# Power.net
KiCad netlist of a schematic drawn in Altium Designer
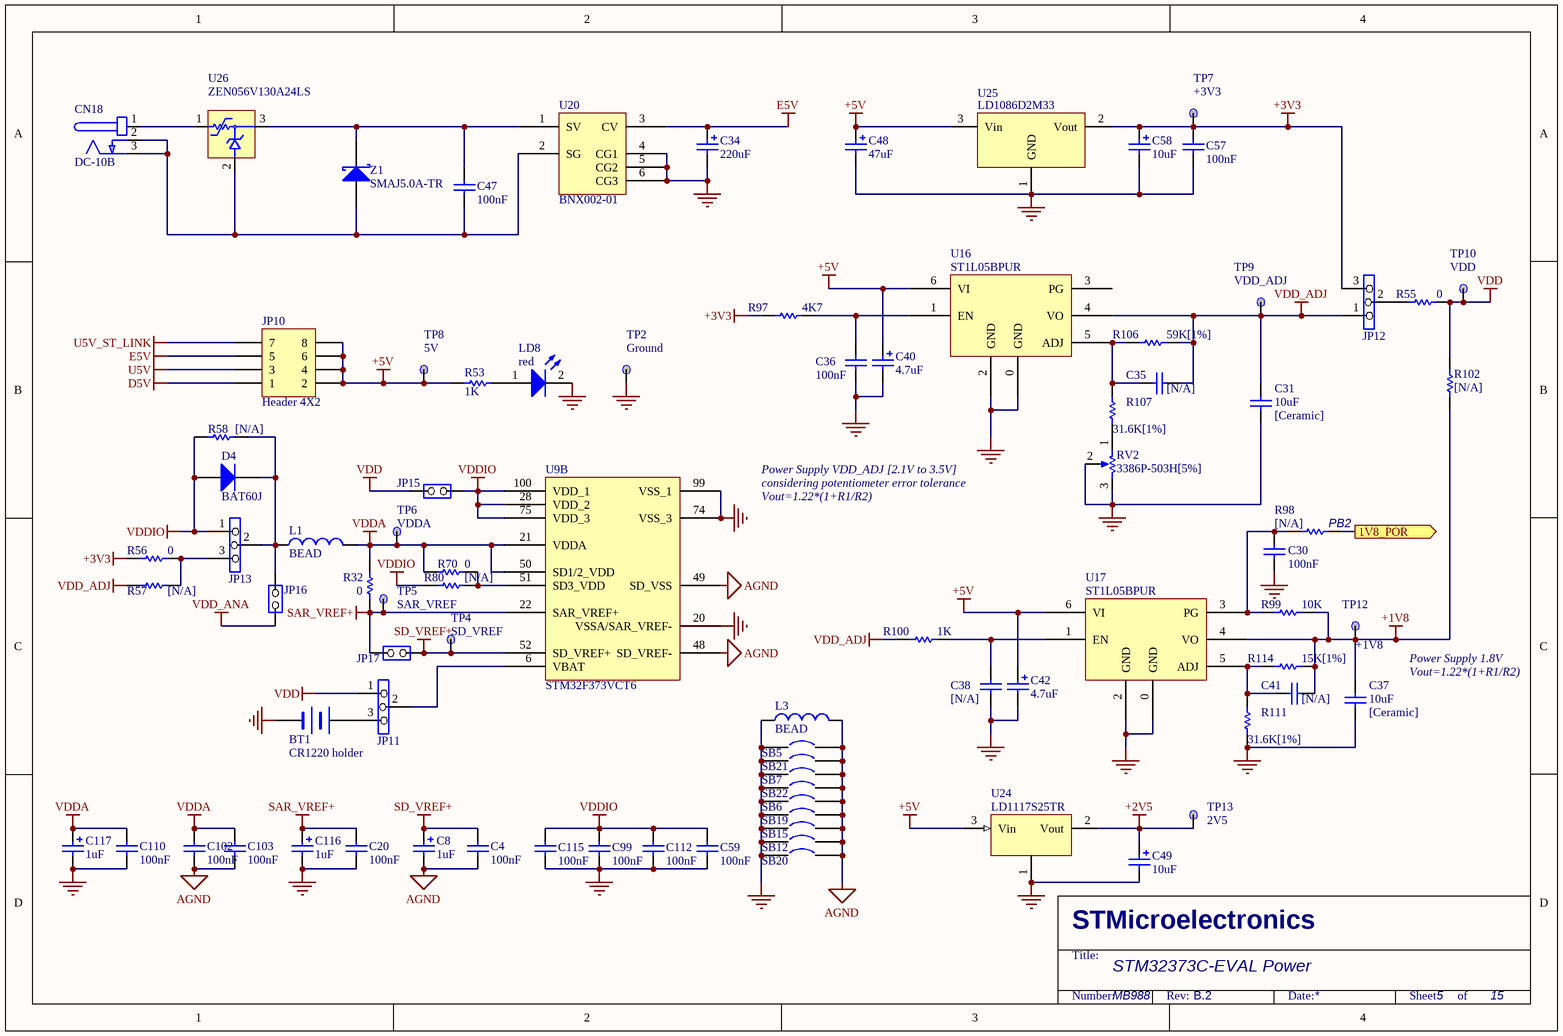
[diagram p0: Power.SchDoc]

(export (version "E")
  (design (tool "Eeschema 10.0.6"))
  (components
    (comp (ref "BT1")
      (value "CR1220 holder")
      (footprint "LI1220_1")
      (description "Battery")
      (libsource (lib "*") (part "BATTERY"))
    )
    (comp (ref "C4")
      (value "100nF")
      (footprint "0603C")
      (description "Capacitor")
      (fields (field (name "PUBLISHER") "Altium Limited"))
      (libsource (lib "Miscellaneous Devices") (part "Cap"))
    )
    (comp (ref "C8")
      (value "1uF")
      (footprint "TAN-A")
      (description "Polarized Capacitor (Radial)")
      (fields (field (name "PUBLISHER") "Altium Limited"))
      (libsource (lib "Miscellaneous Devices") (part "Cap Pol1"))
    )
    (comp (ref "C20")
      (value "100nF")
      (footprint "0603C")
      (description "Capacitor")
      (fields (field (name "PUBLISHER") "Altium Limited"))
      (libsource (lib "Miscellaneous Devices") (part "Cap"))
    )
    (comp (ref "C30")
      (value "100nF")
      (footprint "0603C")
      (description "Capacitor")
      (fields (field (name "PUBLISHER") "Altium Limited"))
      (libsource (lib "Miscellaneous Devices") (part "Cap"))
    )
    (comp (ref "C31")
      (value "10uF")
      (footprint "0805C")
      (description "Capacitor")
      (fields (field (name "PUBLISHER") "Altium Limited"))
      (libsource (lib "Miscellaneous Devices") (part "Cap"))
    )
    (comp (ref "C34")
      (value "220uF")
      (footprint "C310M")
      (description "Polarized Capacitor (Radial)")
      (fields (field (name "PUBLISHER") "Altium Limited"))
      (libsource (lib "Miscellaneous Devices") (part "Cap Pol1"))
    )
    (comp (ref "C35")
      (value "[N/A]")
      (footprint "0603C")
      (description "Capacitor")
      (fields (field (name "PUBLISHER") "Altium Limited"))
      (libsource (lib "Miscellaneous Devices") (part "Cap"))
    )
    (comp (ref "C36")
      (value "100nF")
      (footprint "0603C")
      (description "Capacitor")
      (fields (field (name "PUBLISHER") "Altium Limited"))
      (libsource (lib "Miscellaneous Devices") (part "Cap"))
    )
    (comp (ref "C37")
      (value "10uF")
      (footprint "0805C")
      (description "Capacitor")
      (fields (field (name "PUBLISHER") "Altium Limited"))
      (libsource (lib "Miscellaneous Devices") (part "Cap"))
    )
    (comp (ref "C38")
      (value "[N/A]")
      (footprint "0603C")
      (description "Capacitor")
      (fields (field (name "PUBLISHER") "Altium Limited"))
      (libsource (lib "Miscellaneous Devices") (part "Cap"))
    )
    (comp (ref "C40")
      (value "4.7uF")
      (footprint "TAN-A")
      (description "Polarized Capacitor (Radial)")
      (fields (field (name "PUBLISHER") "Altium Limited"))
      (libsource (lib "*") (part "Cap Pol1"))
    )
    (comp (ref "C41")
      (value "[N/A]")
      (footprint "0603C")
      (description "Capacitor")
      (fields (field (name "PUBLISHER") "Altium Limited"))
      (libsource (lib "Miscellaneous Devices") (part "Cap"))
    )
    (comp (ref "C42")
      (value "4.7uF")
      (footprint "TAN-A")
      (description "Polarized Capacitor (Radial)")
      (fields (field (name "PUBLISHER") "Altium Limited"))
      (libsource (lib "*") (part "Cap Pol1"))
    )
    (comp (ref "C47")
      (value "100nF")
      (footprint "0603C")
      (description "Capacitor")
      (fields (field (name "PUBLISHER") "Altium Limited"))
      (libsource (lib "Miscellaneous Devices") (part "CAP"))
    )
    (comp (ref "C48")
      (value "47uF")
      (footprint "C200M")
      (description "Polarized Capacitor (Radial)")
      (fields (field (name "PUBLISHER") "Altium Limited"))
      (libsource (lib "Miscellaneous Devices") (part "Cap Pol1"))
    )
    (comp (ref "C49")
      (value "10uF")
      (footprint "TAN-A")
      (description "Polarized Capacitor (Radial)")
      (fields (field (name "PUBLISHER") "Altium Limited"))
      (libsource (lib "Miscellaneous Devices") (part "Cap Pol1"))
    )
    (comp (ref "C57")
      (value "100nF")
      (footprint "0603C")
      (description "Capacitor")
      (fields (field (name "PUBLISHER") "Altium Limited"))
      (libsource (lib "Miscellaneous Devices") (part "Cap"))
    )
    (comp (ref "C58")
      (value "10uF")
      (footprint "TAN-A")
      (description "Polarized Capacitor (Radial)")
      (fields (field (name "PUBLISHER") "Altium Limited"))
      (libsource (lib "Miscellaneous Devices") (part "Cap Pol1"))
    )
    (comp (ref "C59")
      (value "100nF")
      (footprint "0603C")
      (description "Capacitor")
      (fields (field (name "PUBLISHER") "Altium Limited"))
      (libsource (lib "Miscellaneous Devices") (part "CAP"))
    )
    (comp (ref "C99")
      (value "100nF")
      (footprint "0603C")
      (description "Capacitor")
      (fields (field (name "PUBLISHER") "Altium Limited"))
      (libsource (lib "Miscellaneous Devices") (part "CAP"))
    )
    (comp (ref "C102")
      (value "100nF")
      (footprint "0603C")
      (description "Capacitor")
      (fields (field (name "PUBLISHER") "Altium Limited"))
      (libsource (lib "Miscellaneous Devices") (part "Cap"))
    )
    (comp (ref "C103")
      (value "100nF")
      (footprint "0603C")
      (description "Capacitor")
      (fields (field (name "PUBLISHER") "Altium Limited"))
      (libsource (lib "Miscellaneous Devices") (part "Cap"))
    )
    (comp (ref "C110")
      (value "100nF")
      (footprint "0603C")
      (description "Capacitor")
      (fields (field (name "PUBLISHER") "Altium Limited"))
      (libsource (lib "Miscellaneous Devices") (part "Cap"))
    )
    (comp (ref "C112")
      (value "100nF")
      (footprint "0603C")
      (description "Capacitor")
      (fields (field (name "PUBLISHER") "Altium Limited"))
      (libsource (lib "Miscellaneous Devices") (part "CAP"))
    )
    (comp (ref "C115")
      (value "100nF")
      (footprint "0603C")
      (description "Capacitor")
      (fields (field (name "PUBLISHER") "Altium Limited"))
      (libsource (lib "Miscellaneous Devices") (part "CAP"))
    )
    (comp (ref "C116")
      (value "1uF")
      (footprint "TAN-A")
      (description "Polarized Capacitor (Radial)")
      (fields (field (name "PUBLISHER") "Altium Limited"))
      (libsource (lib "Miscellaneous Devices") (part "Cap Pol1"))
    )
    (comp (ref "C117")
      (value "1uF")
      (footprint "TAN-A")
      (description "Polarized Capacitor (Radial)")
      (fields (field (name "PUBLISHER") "Altium Limited"))
      (libsource (lib "Miscellaneous Devices") (part "Cap Pol1"))
    )
    (comp (ref "CN18") (value "DC-10B") (footprint "DC10B") (libsource (lib "STR910_SCHLIB") (part "PJ202A")))
    (comp (ref "D4")
      (value "BAT60J")
      (footprint "SOD-323")
      (description "Default Diode")
      (fields (field (name "PUBLISHER") "Altium Limited"))
      (libsource (lib "Miscellaneous Devices") (part "Diode"))
    )
    (comp (ref "JP10")
      (value "Header 4X2")
      (footprint "2*4P")
      (description "Header, 4-Pin, Dual row")
      (fields (field (name "PUBLISHER") "Altium Limited"))
      (libsource (lib "Miscellaneous Connectors") (part "Header 4X2"))
    )
    (comp (ref "JP11") (value "~") (footprint "SIP3") (libsource (lib "") (part "Jumper3_1")))
    (comp (ref "JP12") (value "~") (footprint "SIP3") (libsource (lib "STR910_SCHLIB") (part "Jumper3")))
    (comp (ref "JP13") (value "~") (footprint "SIP3") (libsource (lib "STR910_SCHLIB") (part "Jumper3")))
    (comp (ref "JP15") (value "~") (footprint "SIP2") (libsource (lib "*") (part "JP2")))
    (comp (ref "JP16") (value "~") (footprint "SIP2") (libsource (lib "*") (part "JP2")))
    (comp (ref "JP17") (value "~") (footprint "SIP2") (libsource (lib "*") (part "JP2")))
    (comp (ref "L1")
      (value "BEAD")
      (footprint "0603L")
      (description "Inductor")
      (fields (field (name "PUBLISHER") "Altium Limited"))
      (libsource (lib "Miscellaneous Devices") (part "Inductor"))
    )
    (comp (ref "L3")
      (value "BEAD")
      (footprint "0603L")
      (description "Inductor")
      (fields (field (name "PUBLISHER") "Altium Limited"))
      (libsource (lib "Miscellaneous Devices") (part "Inductor"))
    )
    (comp (ref "LD8")
      (value "red")
      (footprint "0603D")
      (description "Typical RED, GREEN, YELLOW, AMBER GaAs LED")
      (fields (field (name "PUBLISHER") "Altium Limited"))
      (libsource (lib "Miscellaneous Devices") (part "LED2"))
    )
    (comp (ref "R32")
      (value "0")
      (footprint "0603R")
      (description "Resistor")
      (fields (field (name "PUBLISHER") "Altium Limited"))
      (libsource (lib "Miscellaneous Devices") (part "Res1"))
    )
    (comp (ref "R53")
      (value "1K")
      (footprint "0603R")
      (description "Resistor")
      (fields (field (name "PUBLISHER") "Altium Limited"))
      (libsource (lib "Miscellaneous Devices") (part "res1"))
    )
    (comp (ref "R55")
      (value "0")
      (footprint "0603R")
      (description "Resistor")
      (fields (field (name "PUBLISHER") "Altium Limited"))
      (libsource (lib "Miscellaneous Devices") (part "Res1"))
    )
    (comp (ref "R56")
      (value "0")
      (footprint "0603R")
      (description "Resistor")
      (fields (field (name "PUBLISHER") "Altium Limited"))
      (libsource (lib "Miscellaneous Devices") (part "Res1"))
    )
    (comp (ref "R57")
      (value "[N/A]")
      (footprint "0603R")
      (description "Resistor")
      (fields (field (name "PUBLISHER") "Altium Limited"))
      (libsource (lib "Miscellaneous Devices") (part "Res1"))
    )
    (comp (ref "R58")
      (value "[N/A]")
      (footprint "0603R")
      (description "Resistor")
      (fields (field (name "PUBLISHER") "Altium Limited"))
      (libsource (lib "Miscellaneous Devices") (part "Res1"))
    )
    (comp (ref "R70")
      (value "0")
      (footprint "0603R")
      (description "Resistor")
      (fields (field (name "PUBLISHER") "Altium Limited"))
      (libsource (lib "Miscellaneous Devices") (part "Res1"))
    )
    (comp (ref "R80")
      (value "[N/A]")
      (footprint "0603R")
      (description "Resistor")
      (fields (field (name "PUBLISHER") "Altium Limited"))
      (libsource (lib "Miscellaneous Devices") (part "Res1"))
    )
    (comp (ref "R97")
      (value "4K7")
      (footprint "0603R")
      (description "Resistor")
      (fields (field (name "PUBLISHER") "Altium Limited"))
      (libsource (lib "Miscellaneous Devices") (part "res1"))
    )
    (comp (ref "R98")
      (value "[N/A]")
      (footprint "0603R")
      (description "Resistor")
      (fields (field (name "PUBLISHER") "Altium Limited"))
      (libsource (lib "Miscellaneous Devices") (part "Res1"))
    )
    (comp (ref "R99")
      (value "10K")
      (footprint "0603R")
      (description "Resistor")
      (fields (field (name "PUBLISHER") "Altium Limited"))
      (libsource (lib "Miscellaneous Devices") (part "res1"))
    )
    (comp (ref "R100")
      (value "1K")
      (footprint "0603R")
      (description "Resistor")
      (fields (field (name "PUBLISHER") "Altium Limited"))
      (libsource (lib "Miscellaneous Devices") (part "res1"))
    )
    (comp (ref "R102")
      (value "[N/A]")
      (footprint "0603R")
      (description "Resistor")
      (fields (field (name "PUBLISHER") "Altium Limited"))
      (libsource (lib "Miscellaneous Devices") (part "Res1"))
    )
    (comp (ref "R106")
      (value "59K[1%]")
      (footprint "0603R")
      (description "Resistor")
      (fields (field (name "PUBLISHER") "Altium Limited"))
      (libsource (lib "Miscellaneous Devices") (part "Res1"))
    )
    (comp (ref "R107")
      (value "31.6K[1%]")
      (footprint "0603R")
      (description "Resistor")
      (fields (field (name "PUBLISHER") "Altium Limited"))
      (libsource (lib "Miscellaneous Devices") (part "Res1"))
    )
    (comp (ref "R111")
      (value "31.6K[1%]")
      (footprint "0603R")
      (description "Resistor")
      (fields (field (name "PUBLISHER") "Altium Limited"))
      (libsource (lib "Miscellaneous Devices") (part "Res1"))
    )
    (comp (ref "R114")
      (value "15K[1%]")
      (footprint "0603R")
      (description "Resistor")
      (fields (field (name "PUBLISHER") "Altium Limited"))
      (libsource (lib "Miscellaneous Devices") (part "Res1"))
    )
    (comp (ref "RV2")
      (value "3386P-503H[5%]")
      (footprint "3296W")
      (libsource (lib "STR910_SCHLIB") (part "RV"))
    )
    (comp (ref "SB5")
      (value "~")
      (footprint "JP2_SMD")
      (description "Circuit Breaker")
      (fields (field (name "PUBLISHER") "Altium Limited"))
      (libsource (lib "Miscellaneous Devices") (part "Circuit Breaker"))
    )
    (comp (ref "SB6")
      (value "~")
      (footprint "JP2_SMD")
      (description "Circuit Breaker")
      (fields (field (name "PUBLISHER") "Altium Limited"))
      (libsource (lib "Miscellaneous Devices") (part "Circuit Breaker"))
    )
    (comp (ref "SB7")
      (value "~")
      (footprint "JP2_SMD")
      (description "Circuit Breaker")
      (fields (field (name "PUBLISHER") "Altium Limited"))
      (libsource (lib "Miscellaneous Devices") (part "Circuit Breaker"))
    )
    (comp (ref "SB12")
      (value "~")
      (footprint "JP2_SMD")
      (description "Circuit Breaker")
      (fields (field (name "PUBLISHER") "Altium Limited"))
      (libsource (lib "Miscellaneous Devices") (part "Circuit Breaker"))
    )
    (comp (ref "SB15")
      (value "~")
      (footprint "JP2_SMD")
      (description "Circuit Breaker")
      (fields (field (name "PUBLISHER") "Altium Limited"))
      (libsource (lib "Miscellaneous Devices") (part "Circuit Breaker"))
    )
    (comp (ref "SB19")
      (value "~")
      (footprint "JP2_SMD")
      (description "Circuit Breaker")
      (fields (field (name "PUBLISHER") "Altium Limited"))
      (libsource (lib "Miscellaneous Devices") (part "Circuit Breaker"))
    )
    (comp (ref "SB20")
      (value "~")
      (footprint "JP2_SMD")
      (description "Circuit Breaker")
      (fields (field (name "PUBLISHER") "Altium Limited"))
      (libsource (lib "Miscellaneous Devices") (part "Circuit Breaker"))
    )
    (comp (ref "SB21")
      (value "~")
      (footprint "JP2_SMD")
      (description "Circuit Breaker")
      (fields (field (name "PUBLISHER") "Altium Limited"))
      (libsource (lib "Miscellaneous Devices") (part "Circuit Breaker"))
    )
    (comp (ref "SB22")
      (value "~")
      (footprint "JP2_SMD")
      (description "Circuit Breaker")
      (fields (field (name "PUBLISHER") "Altium Limited"))
      (libsource (lib "Miscellaneous Devices") (part "Circuit Breaker"))
    )
    (comp (ref "TP2") (value "Ground") (footprint "TP") (libsource (lib "*") (part "TP")))
    (comp (ref "TP4") (value "SD_VREF") (footprint "TP") (libsource (lib "*") (part "TP")))
    (comp (ref "TP5") (value "SAR_VREF") (footprint "TP") (libsource (lib "*") (part "TP")))
    (comp (ref "TP6") (value "VDDA") (footprint "TP") (libsource (lib "*") (part "TP")))
    (comp (ref "TP7") (value "+3V3") (footprint "TP") (libsource (lib "*") (part "TP")))
    (comp (ref "TP8") (value "5V") (footprint "TP") (libsource (lib "*") (part "TP")))
    (comp (ref "TP9") (value "VDD_ADJ") (footprint "TP") (libsource (lib "*") (part "TP")))
    (comp (ref "TP10") (value "VDD") (footprint "TP") (libsource (lib "*") (part "TP")))
    (comp (ref "TP12") (value "+1V8") (footprint "TP") (libsource (lib "*") (part "TP")))
    (comp (ref "TP13") (value "2V5") (footprint "TP") (libsource (lib "*") (part "TP")))
    (comp (ref "U9")
      (value "STM32F373VCT6")
      (footprint "IC149-100-025-B5")
      (libsource (lib "MB988") (part "Goldfish"))
    )
    (comp (ref "U16") (value "ST1L05BPUR") (footprint "DFN6(3X3)") (libsource (lib "*") (part "ST1L05")))
    (comp (ref "U17") (value "ST1L05BPUR") (footprint "DFN6(3X3)") (libsource (lib "*") (part "ST1L05")))
    (comp (ref "U20")
      (value "BNX002-01")
      (footprint "BNX001")
      (libsource (lib "STR910_SCHLIB") (part "BNX002"))
    )
    (comp (ref "U24") (value "LD1117S25TR") (footprint "SOT-223") (libsource (lib "*") (part "LD1117")))
    (comp (ref "U25") (value "LD1086D2M33") (footprint "D2PAK/A") (libsource (lib "*") (part "VOLTREG1")))
    (comp (ref "U26")
      (value "ZEN056V130A24LS")
      (footprint "polyzen")
      (libsource (lib "STR910_SCHLIB") (part "ZEN056V130A24LS"))
    )
    (comp (ref "Z1")
      (value "SMAJ5.0A-TR")
      (footprint "1R1C")
      (description "Schottky Diode")
      (fields (field (name "PUBLISHER") "Altium Limited"))
      (libsource (lib "Miscellaneous Devices") (part "D Schottky"))
    )
  )
  (nets
    (net (code "1") (name "+1V8") (class "Default")
      (node (ref "C37") (pin "1") (pinfunction "1_1") (pintype "passive"))
      (node (ref "C41") (pin "2") (pinfunction "2_2") (pintype "passive"))
      (node (ref "R102") (pin "2") (pinfunction "2_2") (pintype "passive"))
      (node (ref "R114") (pin "1") (pinfunction "1_1") (pintype "passive"))
      (node (ref "R99") (pin "2") (pinfunction "2_2") (pintype "passive"))
      (node (ref "TP12") (pin "1") (pinfunction "1_1") (pintype "passive"))
      (node (ref "U17") (pin "4") (pinfunction "VO_4") (pintype "passive"))
    )
    (net (code "2") (name "+2V5") (class "Default")
      (node (ref "C49") (pin "1") (pinfunction "1_1") (pintype "passive"))
      (node (ref "TP13") (pin "1") (pinfunction "1_1") (pintype "passive"))
      (node (ref "U24") (pin "2") (pinfunction "Vout_2") (pintype "power_in"))
    )
    (net (code "3") (name "+3V3") (class "Default")
      (node (ref "C57") (pin "1") (pinfunction "1_1") (pintype "passive"))
      (node (ref "C58") (pin "1") (pinfunction "1_1") (pintype "passive"))
      (node (ref "JP12") (pin "3") (pintype "passive"))
      (node (ref "R56") (pin "2") (pinfunction "2_2") (pintype "passive"))
      (node (ref "R97") (pin "2") (pinfunction "2_2") (pintype "passive"))
      (node (ref "TP7") (pin "1") (pinfunction "1_1") (pintype "passive"))
      (node (ref "U25") (pin "2") (pinfunction "Vout_2") (pintype "passive"))
    )
    (net (code "4") (name "+5V") (class "Default")
      (node (ref "C40") (pin "1") (pinfunction "1_1") (pintype "passive"))
      (node (ref "C42") (pin "1") (pinfunction "1_1") (pintype "passive"))
      (node (ref "C48") (pin "1") (pinfunction "1_1") (pintype "passive"))
      (node (ref "JP10") (pin "2") (pinfunction "2_2") (pintype "passive"))
      (node (ref "JP10") (pin "4") (pinfunction "4_4") (pintype "passive"))
      (node (ref "JP10") (pin "6") (pinfunction "6_6") (pintype "passive"))
      (node (ref "JP10") (pin "8") (pinfunction "8_8") (pintype "passive"))
      (node (ref "R53") (pin "2") (pinfunction "2_2") (pintype "passive"))
      (node (ref "TP8") (pin "1") (pinfunction "1_1") (pintype "passive"))
      (node (ref "U16") (pin "6") (pinfunction "VI_6") (pintype "passive"))
      (node (ref "U17") (pin "6") (pinfunction "VI_6") (pintype "passive"))
      (node (ref "U24") (pin "3") (pinfunction "Vin_3") (pintype "input"))
      (node (ref "U25") (pin "3") (pinfunction "Vin_3") (pintype "passive"))
    )
    (net (code "5") (name "/1V8_POR") (class "Default")
      (node (ref "R98") (pin "1") (pinfunction "1_1") (pintype "passive"))
    )
    (net (code "6") (name "AGND") (class "Default")
      (node (ref "C102") (pin "1") (pinfunction "1_1") (pintype "passive"))
      (node (ref "C103") (pin "1") (pinfunction "1_1") (pintype "passive"))
      (node (ref "C4") (pin "1") (pinfunction "1_1") (pintype "passive"))
      (node (ref "C8") (pin "2") (pinfunction "2_2") (pintype "passive"))
      (node (ref "L3") (pin "2") (pinfunction "2_2") (pintype "passive"))
      (node (ref "SB12") (pin "2") (pinfunction "2_2") (pintype "passive"))
      (node (ref "SB15") (pin "2") (pinfunction "2_2") (pintype "passive"))
      (node (ref "SB19") (pin "2") (pinfunction "2_2") (pintype "passive"))
      (node (ref "SB20") (pin "2") (pinfunction "2_2") (pintype "passive"))
      (node (ref "SB21") (pin "2") (pinfunction "2_2") (pintype "passive"))
      (node (ref "SB22") (pin "2") (pinfunction "2_2") (pintype "passive"))
      (node (ref "SB5") (pin "2") (pinfunction "2_2") (pintype "passive"))
      (node (ref "SB6") (pin "2") (pinfunction "2_2") (pintype "passive"))
      (node (ref "SB7") (pin "2") (pinfunction "2_2") (pintype "passive"))
      (node (ref "U9") (pin "48") (pinfunction "SD_VREF-_48") (pintype "passive"))
      (node (ref "U9") (pin "49") (pinfunction "SD_VSS_49") (pintype "passive"))
    )
    (net (code "7") (name "D5V") (class "Default")
      (node (ref "JP10") (pin "1") (pinfunction "1_1") (pintype "passive"))
    )
    (net (code "8") (name "E5V") (class "Default")
      (node (ref "C34") (pin "1") (pinfunction "1_1") (pintype "passive"))
      (node (ref "JP10") (pin "5") (pinfunction "5_5") (pintype "passive"))
      (node (ref "U20") (pin "3") (pinfunction "CV_3") (pintype "passive"))
    )
    (net (code "9") (name "GND") (class "Default")
      (node (ref "BT1") (pin "2") (pinfunction "-_2") (pintype "passive"))
      (node (ref "C110") (pin "1") (pinfunction "1_1") (pintype "passive"))
      (node (ref "C112") (pin "2") (pinfunction "2_2") (pintype "passive"))
      (node (ref "C115") (pin "2") (pinfunction "2_2") (pintype "passive"))
      (node (ref "C116") (pin "2") (pinfunction "2_2") (pintype "passive"))
      (node (ref "C117") (pin "2") (pinfunction "2_2") (pintype "passive"))
      (node (ref "C20") (pin "1") (pinfunction "1_1") (pintype "passive"))
      (node (ref "C30") (pin "2") (pinfunction "2_2") (pintype "passive"))
      (node (ref "C31") (pin "2") (pinfunction "2_2") (pintype "passive"))
      (node (ref "C34") (pin "2") (pinfunction "2_2") (pintype "passive"))
      (node (ref "C36") (pin "2") (pinfunction "2_2") (pintype "passive"))
      (node (ref "C37") (pin "2") (pinfunction "2_2") (pintype "passive"))
      (node (ref "C38") (pin "2") (pinfunction "2_2") (pintype "passive"))
      (node (ref "C40") (pin "2") (pinfunction "2_2") (pintype "passive"))
      (node (ref "C42") (pin "2") (pinfunction "2_2") (pintype "passive"))
      (node (ref "C48") (pin "2") (pinfunction "2_2") (pintype "passive"))
      (node (ref "C49") (pin "2") (pinfunction "2_2") (pintype "passive"))
      (node (ref "C57") (pin "2") (pinfunction "2_2") (pintype "passive"))
      (node (ref "C58") (pin "2") (pinfunction "2_2") (pintype "passive"))
      (node (ref "C59") (pin "2") (pinfunction "2_2") (pintype "passive"))
      (node (ref "C99") (pin "2") (pinfunction "2_2") (pintype "passive"))
      (node (ref "L3") (pin "1") (pinfunction "1_1") (pintype "passive"))
      (node (ref "LD8") (pin "2") (pinfunction "K_2") (pintype "passive"))
      (node (ref "R111") (pin "2") (pinfunction "2_2") (pintype "passive"))
      (node (ref "RV2") (pin "2") (pinfunction "TAP_2") (pintype "passive"))
      (node (ref "RV2") (pin "3") (pinfunction "TOP_3") (pintype "passive"))
      (node (ref "SB12") (pin "1") (pinfunction "1_1") (pintype "passive"))
      (node (ref "SB15") (pin "1") (pinfunction "1_1") (pintype "passive"))
      (node (ref "SB19") (pin "1") (pinfunction "1_1") (pintype "passive"))
      (node (ref "SB20") (pin "1") (pinfunction "1_1") (pintype "passive"))
      (node (ref "SB21") (pin "1") (pinfunction "1_1") (pintype "passive"))
      (node (ref "SB22") (pin "1") (pinfunction "1_1") (pintype "passive"))
      (node (ref "SB5") (pin "1") (pinfunction "1_1") (pintype "passive"))
      (node (ref "SB6") (pin "1") (pinfunction "1_1") (pintype "passive"))
      (node (ref "SB7") (pin "1") (pinfunction "1_1") (pintype "passive"))
      (node (ref "TP2") (pin "1") (pinfunction "1_1") (pintype "passive"))
      (node (ref "U16") (pin "0") (pinfunction "GND_0") (pintype "passive"))
      (node (ref "U16") (pin "2") (pinfunction "GND_2") (pintype "passive"))
      (node (ref "U17") (pin "0") (pinfunction "GND_0") (pintype "passive"))
      (node (ref "U17") (pin "2") (pinfunction "GND_2") (pintype "passive"))
      (node (ref "U20") (pin "4") (pinfunction "CG1_4") (pintype "passive"))
      (node (ref "U20") (pin "5") (pinfunction "CG2_5") (pintype "passive"))
      (node (ref "U20") (pin "6") (pinfunction "CG3_6") (pintype "passive"))
      (node (ref "U24") (pin "1") (pintype "passive"))
      (node (ref "U25") (pin "1") (pinfunction "GND_1") (pintype "passive"))
      (node (ref "U9") (pin "20") (pinfunction "VSSA/SAR_VREF-_20") (pintype "passive"))
      (node (ref "U9") (pin "74") (pinfunction "VSS_3_74") (pintype "passive"))
      (node (ref "U9") (pin "99") (pinfunction "VSS_1_99") (pintype "passive"))
    )
    (net (code "10") (name "Net-(BT1-+)") (class "Default")
      (node (ref "BT1") (pin "1") (pinfunction "+_1") (pintype "passive"))
      (node (ref "JP11") (pin "3") (pintype "passive"))
    )
    (net (code "11") (name "Net-(CN18-+)") (class "Default")
      (node (ref "CN18") (pin "1") (pinfunction "+_1") (pintype "passive"))
      (node (ref "U26") (pin "1") (pintype "passive"))
    )
    (net (code "12") (name "Net-(D4-K)") (class "Default")
      (node (ref "D4") (pin "2") (pinfunction "K_2") (pintype "passive"))
      (node (ref "JP13") (pin "2") (pintype "passive"))
      (node (ref "JP16") (pin "2") (pinfunction "NO_2") (pintype "passive"))
      (node (ref "L1") (pin "1") (pinfunction "1_1") (pintype "passive"))
      (node (ref "R58") (pin "2") (pinfunction "2_2") (pintype "passive"))
    )
    (net (code "13") (name "Net-(JP12-Pad2)") (class "Default")
      (node (ref "JP12") (pin "2") (pintype "passive"))
      (node (ref "R55") (pin "2") (pinfunction "2_2") (pintype "passive"))
    )
    (net (code "14") (name "Net-(JP13-Pad3)") (class "Default")
      (node (ref "JP13") (pin "3") (pintype "passive"))
      (node (ref "R56") (pin "1") (pinfunction "1_1") (pintype "passive"))
      (node (ref "R57") (pin "1") (pinfunction "1_1") (pintype "passive"))
    )
    (net (code "15") (name "Net-(LD8-A)") (class "Default")
      (node (ref "LD8") (pin "1") (pinfunction "A_1") (pintype "passive"))
      (node (ref "R53") (pin "1") (pinfunction "1_1") (pintype "passive"))
    )
    (net (code "16") (name "Net-(RV2-BOT)") (class "Default")
      (node (ref "R107") (pin "2") (pinfunction "2_2") (pintype "passive"))
      (node (ref "RV2") (pin "1") (pinfunction "BOT_1") (pintype "passive"))
    )
    (net (code "17") (name "Net-(U9B-SD3_VDD)") (class "Default")
      (node (ref "R70") (pin "2") (pinfunction "2_2") (pintype "passive"))
      (node (ref "R80") (pin "2") (pinfunction "2_2") (pintype "passive"))
      (node (ref "U9") (pin "51") (pinfunction "SD3_VDD_51") (pintype "passive"))
    )
    (net (code "18") (name "Net-(U9B-VBAT)") (class "Default")
      (node (ref "JP11") (pin "2") (pintype "passive"))
      (node (ref "U9") (pin "6") (pinfunction "VBAT_6") (pintype "passive"))
    )
    (net (code "19") (name "Net-(U16-ADJ)") (class "Default")
      (node (ref "C35") (pin "1") (pinfunction "1_1") (pintype "passive"))
      (node (ref "R106") (pin "2") (pinfunction "2_2") (pintype "passive"))
      (node (ref "R107") (pin "1") (pinfunction "1_1") (pintype "passive"))
      (node (ref "U16") (pin "5") (pinfunction "ADJ_5") (pintype "passive"))
    )
    (net (code "20") (name "Net-(U16-EN)") (class "Default")
      (node (ref "C36") (pin "1") (pinfunction "1_1") (pintype "passive"))
      (node (ref "R97") (pin "1") (pinfunction "1_1") (pintype "passive"))
      (node (ref "U16") (pin "1") (pinfunction "EN_1") (pintype "passive"))
    )
    (net (code "21") (name "Net-(U17-ADJ)") (class "Default")
      (node (ref "C41") (pin "1") (pinfunction "1_1") (pintype "passive"))
      (node (ref "R111") (pin "1") (pinfunction "1_1") (pintype "passive"))
      (node (ref "R114") (pin "2") (pinfunction "2_2") (pintype "passive"))
      (node (ref "U17") (pin "5") (pinfunction "ADJ_5") (pintype "passive"))
    )
    (net (code "22") (name "Net-(U17-EN)") (class "Default")
      (node (ref "C38") (pin "1") (pinfunction "1_1") (pintype "passive"))
      (node (ref "R100") (pin "1") (pinfunction "1_1") (pintype "passive"))
      (node (ref "U17") (pin "1") (pinfunction "EN_1") (pintype "passive"))
    )
    (net (code "23") (name "Net-(U17-PG)") (class "Default")
      (node (ref "C30") (pin "1") (pinfunction "1_1") (pintype "passive"))
      (node (ref "R98") (pin "2") (pinfunction "2_2") (pintype "passive"))
      (node (ref "R99") (pin "1") (pinfunction "1_1") (pintype "passive"))
      (node (ref "U17") (pin "3") (pinfunction "PG_3") (pintype "passive"))
    )
    (net (code "24") (name "Net-(U20-SG)") (class "Default")
      (node (ref "C47") (pin "2") (pinfunction "2_2") (pintype "passive"))
      (node (ref "CN18") (pin "2") (pinfunction "GND_2") (pintype "passive"))
      (node (ref "CN18") (pin "3") (pinfunction "GND_3") (pintype "passive"))
      (node (ref "U20") (pin "2") (pinfunction "SG_2") (pintype "passive"))
      (node (ref "U26") (pin "2") (pintype "passive"))
      (node (ref "Z1") (pin "1") (pinfunction "A_1") (pintype "passive"))
    )
    (net (code "25") (name "Net-(U20-SV)") (class "Default")
      (node (ref "C47") (pin "1") (pinfunction "1_1") (pintype "passive"))
      (node (ref "U20") (pin "1") (pinfunction "SV_1") (pintype "passive"))
      (node (ref "U26") (pin "3") (pintype "passive"))
      (node (ref "Z1") (pin "2") (pinfunction "K_2") (pintype "passive"))
    )
    (net (code "26") (name "SAR_VREF+") (class "Default")
      (node (ref "C116") (pin "1") (pinfunction "1_1") (pintype "passive"))
      (node (ref "C20") (pin "2") (pinfunction "2_2") (pintype "passive"))
      (node (ref "JP17") (pin "2") (pinfunction "NO_2") (pintype "passive"))
      (node (ref "R32") (pin "2") (pinfunction "2_2") (pintype "passive"))
      (node (ref "TP5") (pin "1") (pinfunction "1_1") (pintype "passive"))
      (node (ref "U9") (pin "22") (pinfunction "SAR_VREF+_22") (pintype "passive"))
    )
    (net (code "27") (name "SD_VREF+") (class "Default")
      (node (ref "C4") (pin "2") (pinfunction "2_2") (pintype "passive"))
      (node (ref "C8") (pin "1") (pinfunction "1_1") (pintype "passive"))
      (node (ref "JP17") (pin "1") (pinfunction "COMMON_1") (pintype "passive"))
      (node (ref "TP4") (pin "1") (pinfunction "1_1") (pintype "passive"))
      (node (ref "U9") (pin "52") (pinfunction "SD_VREF+_52") (pintype "passive"))
    )
    (net (code "28") (name "U5V") (class "Default")
      (node (ref "JP10") (pin "3") (pinfunction "3_3") (pintype "passive"))
    )
    (net (code "29") (name "U5V_ST_LINK") (class "Default")
      (node (ref "JP10") (pin "7") (pinfunction "7_7") (pintype "passive"))
    )
    (net (code "30") (name "VDD") (class "Default")
      (node (ref "JP11") (pin "1") (pintype "passive"))
      (node (ref "JP15") (pin "2") (pinfunction "NO_2") (pintype "passive"))
      (node (ref "R102") (pin "1") (pinfunction "1_1") (pintype "passive"))
      (node (ref "R55") (pin "1") (pinfunction "1_1") (pintype "passive"))
      (node (ref "TP10") (pin "1") (pinfunction "1_1") (pintype "passive"))
    )
    (net (code "31") (name "VDDA") (class "Default")
      (node (ref "C102") (pin "2") (pinfunction "2_2") (pintype "passive"))
      (node (ref "C103") (pin "2") (pinfunction "2_2") (pintype "passive"))
      (node (ref "C110") (pin "2") (pinfunction "2_2") (pintype "passive"))
      (node (ref "C117") (pin "1") (pinfunction "1_1") (pintype "passive"))
      (node (ref "L1") (pin "2") (pinfunction "2_2") (pintype "passive"))
      (node (ref "R32") (pin "1") (pinfunction "1_1") (pintype "passive"))
      (node (ref "R70") (pin "1") (pinfunction "1_1") (pintype "passive"))
      (node (ref "TP6") (pin "1") (pinfunction "1_1") (pintype "passive"))
      (node (ref "U9") (pin "21") (pinfunction "VDDA_21") (pintype "passive"))
      (node (ref "U9") (pin "50") (pinfunction "SD1/2_VDD_50") (pintype "passive"))
    )
    (net (code "32") (name "VDDIO") (class "Default")
      (node (ref "C112") (pin "1") (pinfunction "1_1") (pintype "passive"))
      (node (ref "C115") (pin "1") (pinfunction "1_1") (pintype "passive"))
      (node (ref "C59") (pin "1") (pinfunction "1_1") (pintype "passive"))
      (node (ref "C99") (pin "1") (pinfunction "1_1") (pintype "passive"))
      (node (ref "D4") (pin "1") (pinfunction "A_1") (pintype "passive"))
      (node (ref "JP13") (pin "1") (pintype "passive"))
      (node (ref "JP15") (pin "1") (pinfunction "COMMON_1") (pintype "passive"))
      (node (ref "R58") (pin "1") (pinfunction "1_1") (pintype "passive"))
      (node (ref "R80") (pin "1") (pinfunction "1_1") (pintype "passive"))
      (node (ref "U9") (pin "100") (pinfunction "VDD_1_100") (pintype "passive"))
      (node (ref "U9") (pin "28") (pinfunction "VDD_2_28") (pintype "passive"))
      (node (ref "U9") (pin "75") (pinfunction "VDD_3_75") (pintype "passive"))
    )
    (net (code "33") (name "VDD_ADJ") (class "Default")
      (node (ref "C31") (pin "1") (pinfunction "1_1") (pintype "passive"))
      (node (ref "C35") (pin "2") (pinfunction "2_2") (pintype "passive"))
      (node (ref "JP12") (pin "1") (pintype "passive"))
      (node (ref "R100") (pin "2") (pinfunction "2_2") (pintype "passive"))
      (node (ref "R106") (pin "1") (pinfunction "1_1") (pintype "passive"))
      (node (ref "R57") (pin "2") (pinfunction "2_2") (pintype "passive"))
      (node (ref "TP9") (pin "1") (pinfunction "1_1") (pintype "passive"))
      (node (ref "U16") (pin "4") (pinfunction "VO_4") (pintype "passive"))
    )
    (net (code "34") (name "VDD_ANA") (class "Default")
      (node (ref "JP16") (pin "1") (pinfunction "COMMON_1") (pintype "passive"))
    )
    (net (code "35") (name "unconnected-(U16-PG-Pad3)") (class "Default")
      (node (ref "U16") (pin "3") (pinfunction "PG_3") (pintype "passive"))
    )
  )
)
